# HARE_schematic_10172017.net
KiCad netlist of a schematic drawn in EAGLE
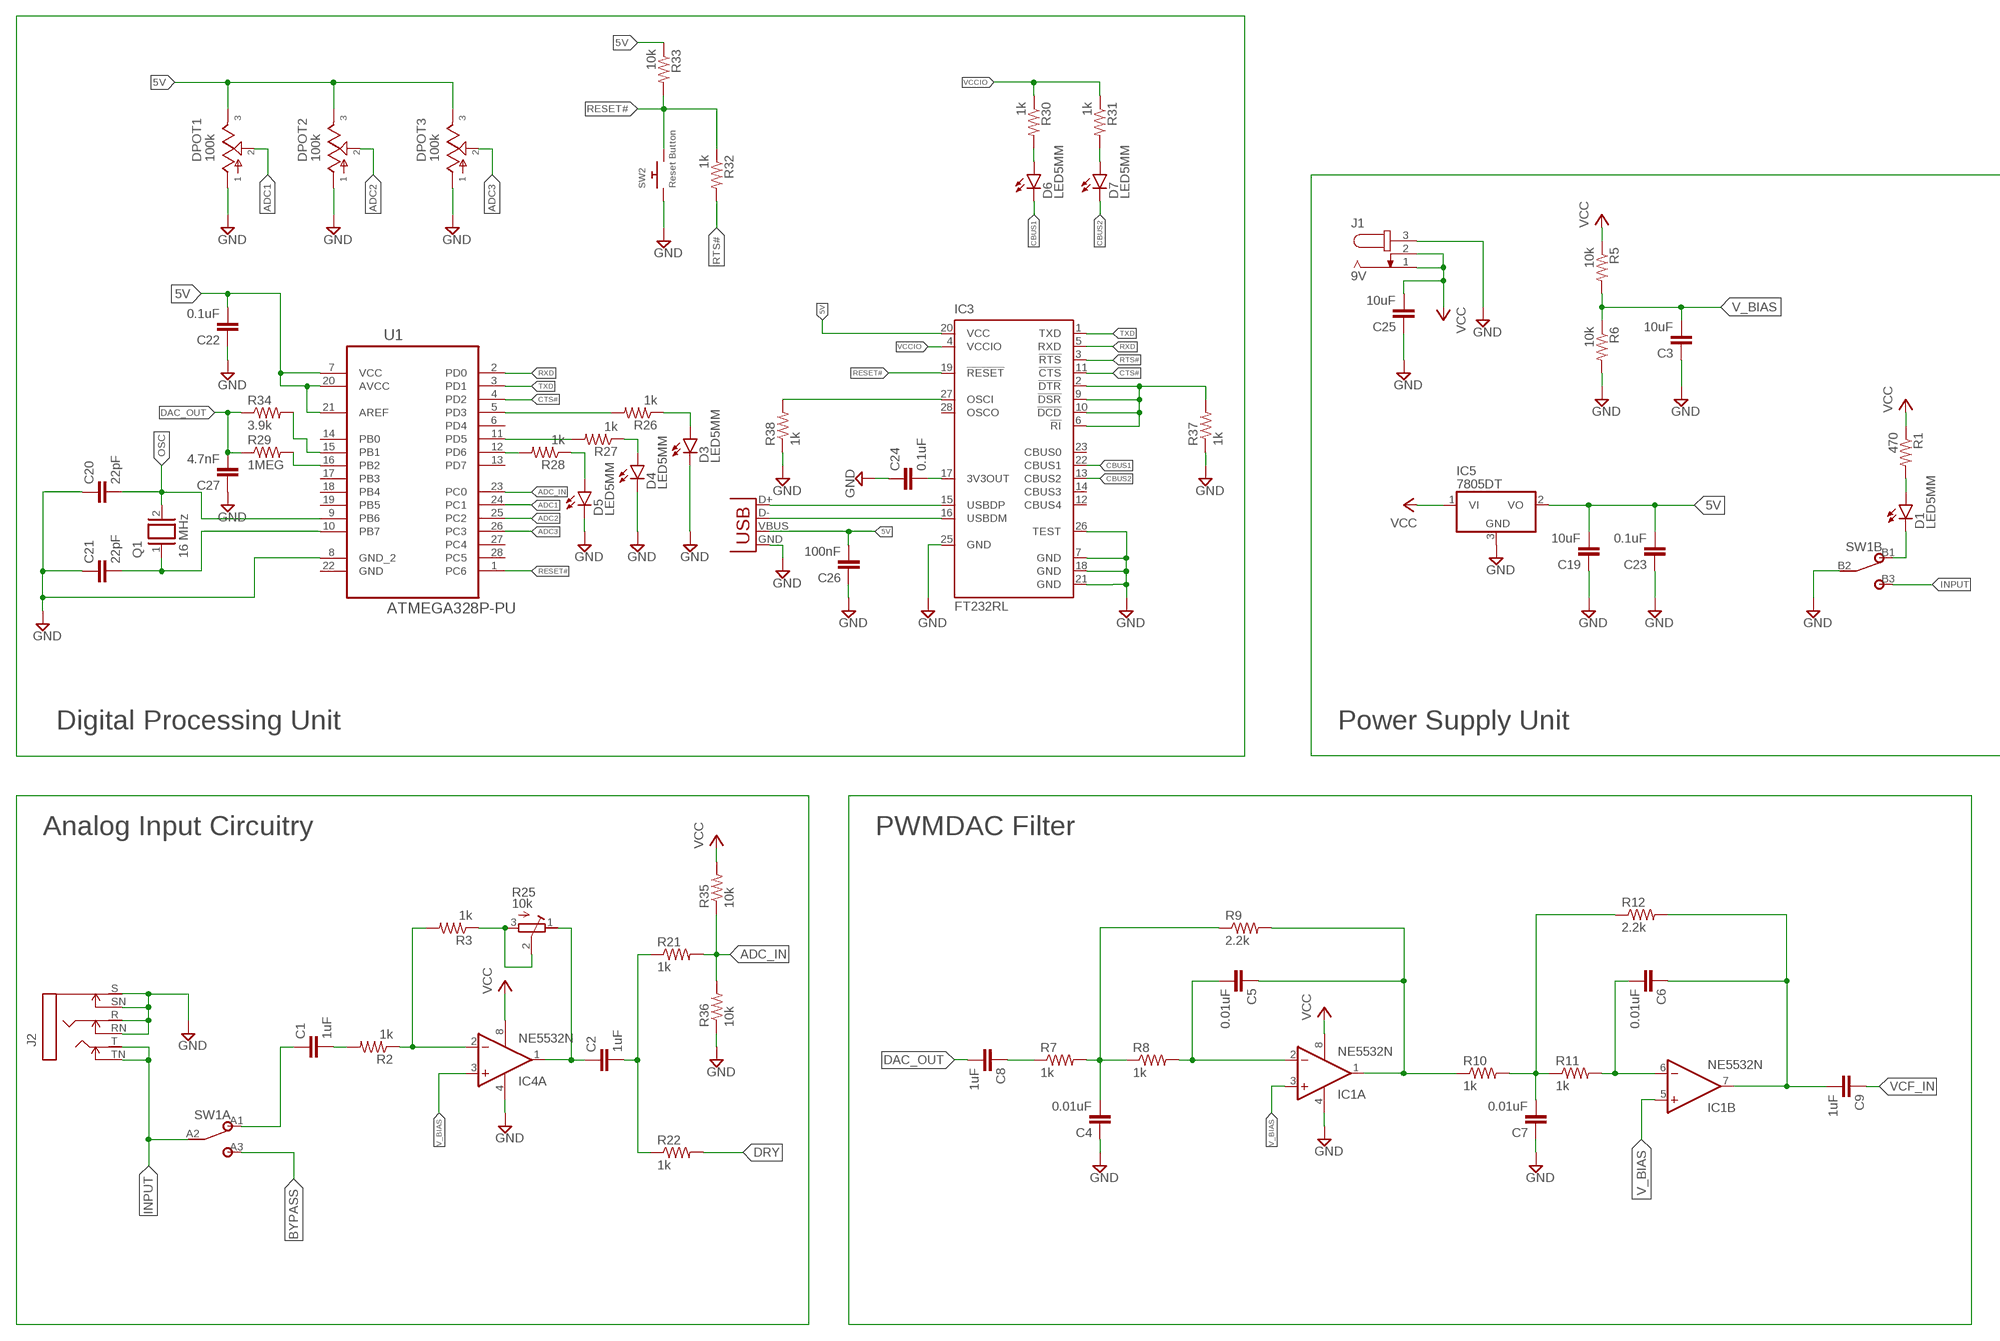
[diagram p0: schematic, sheet 1, part 1 of 2]
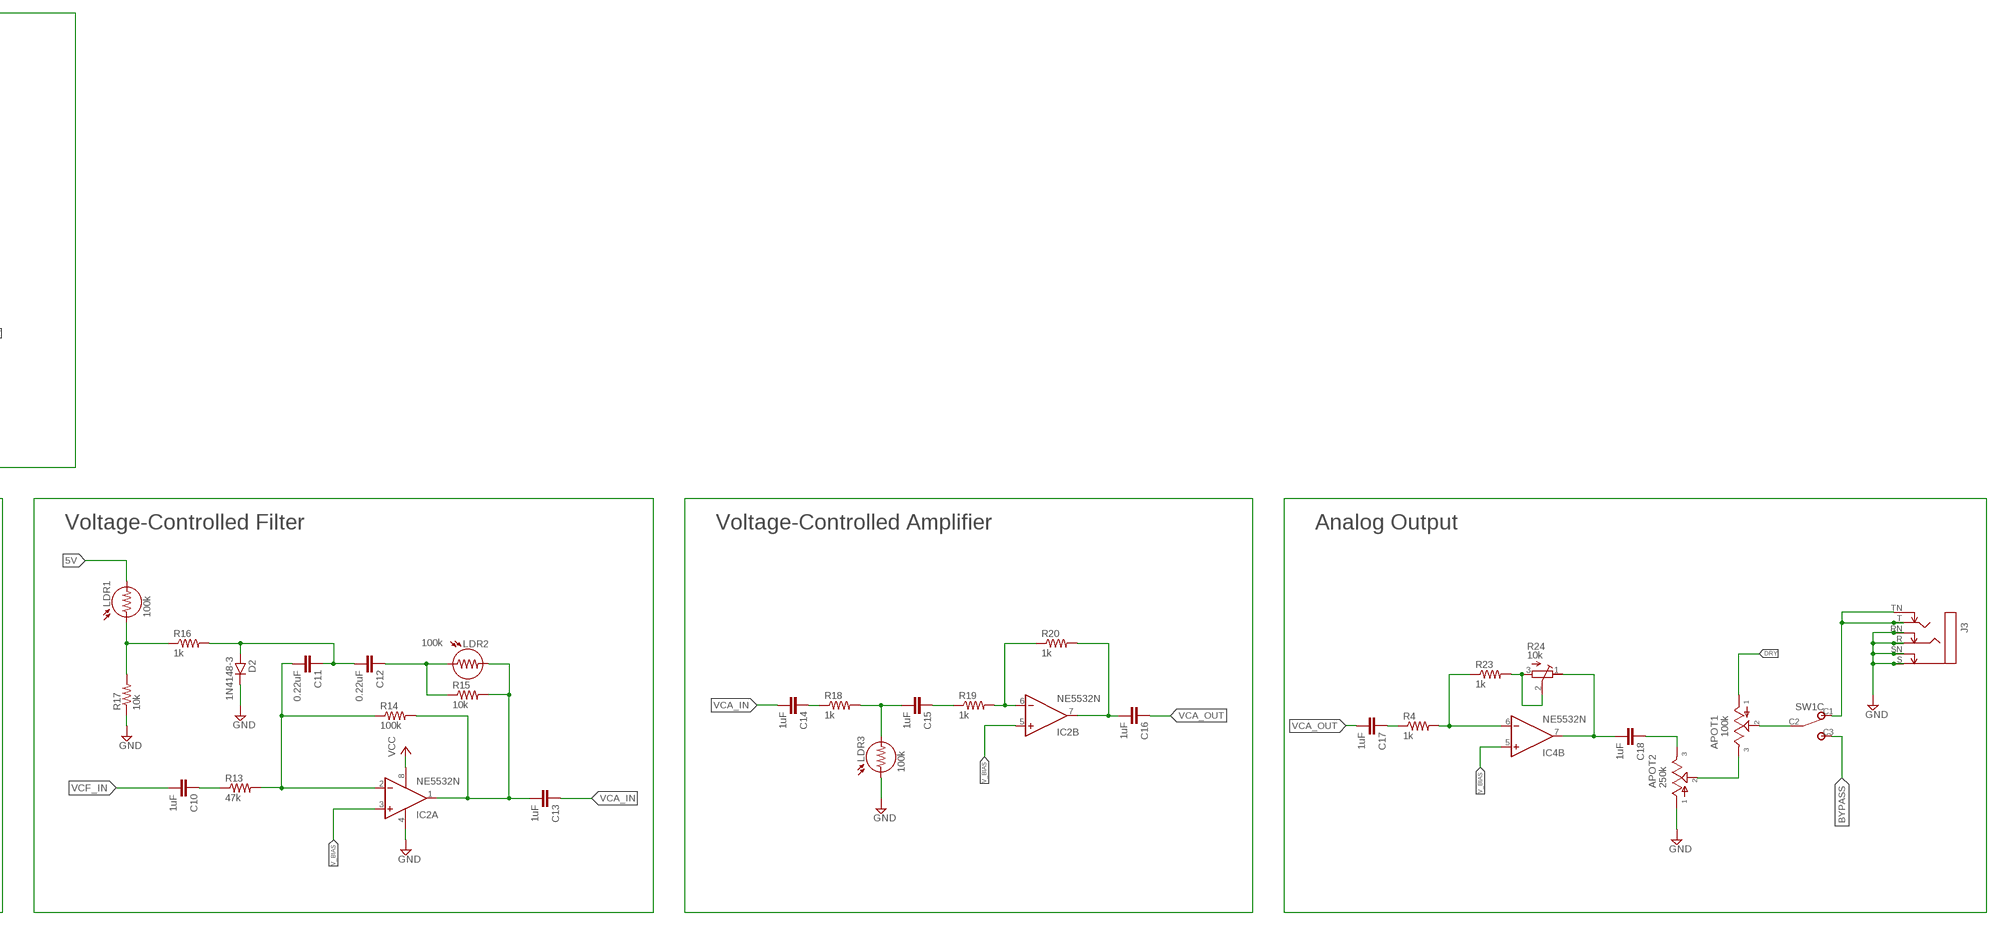
[diagram p1: schematic, sheet 1, part 2 of 2]

(export (version "E")
  (design (tool "Eeschema 10.0.6"))
  (components
    (comp (ref "APOT1")
      (value "100k")
      (footprint "eagle-import:16MM-SQUARE")
      (libsource (lib "eagle-import") (part "POTS"))
    )
    (comp (ref "APOT2")
      (value "250k")
      (footprint "eagle-import:16MM-SQUARE")
      (libsource (lib "eagle-import") (part "POTS"))
    )
    (comp (ref "C1")
      (value "1uF")
      (footprint "eagle-import:C0805K")
      (libsource (lib "eagle-import") (part "C-EUC0805K"))
    )
    (comp (ref "C2")
      (value "1uF")
      (footprint "eagle-import:C0805K")
      (libsource (lib "eagle-import") (part "C-EUC0805K"))
    )
    (comp (ref "C3")
      (value "10uF")
      (footprint "eagle-import:C0805K")
      (libsource (lib "eagle-import") (part "C-EUC0805K"))
    )
    (comp (ref "C4")
      (value "0.01uF")
      (footprint "eagle-import:C0805K")
      (libsource (lib "eagle-import") (part "C-EUC0805K"))
    )
    (comp (ref "C5")
      (value "0.01uF")
      (footprint "eagle-import:C0805K")
      (libsource (lib "eagle-import") (part "C-EUC0805K"))
    )
    (comp (ref "C6")
      (value "0.01uF")
      (footprint "eagle-import:C0805K")
      (libsource (lib "eagle-import") (part "C-EUC0805K"))
    )
    (comp (ref "C7")
      (value "0.01uF")
      (footprint "eagle-import:C0805K")
      (libsource (lib "eagle-import") (part "C-EUC0805K"))
    )
    (comp (ref "C8")
      (value "1uF")
      (footprint "eagle-import:C0805K")
      (libsource (lib "eagle-import") (part "C-EUC0805K"))
    )
    (comp (ref "C9")
      (value "1uF")
      (footprint "eagle-import:C0805K")
      (libsource (lib "eagle-import") (part "C-EUC0805K"))
    )
    (comp (ref "C10")
      (value "1uF")
      (footprint "eagle-import:C0805K")
      (libsource (lib "eagle-import") (part "C-EUC0805K"))
    )
    (comp (ref "C11")
      (value "0.22uF")
      (footprint "eagle-import:C0805K")
      (libsource (lib "eagle-import") (part "C-EUC0805K"))
    )
    (comp (ref "C12")
      (value "0.22uF")
      (footprint "eagle-import:C0805K")
      (libsource (lib "eagle-import") (part "C-EUC0805K"))
    )
    (comp (ref "C13")
      (value "1uF")
      (footprint "eagle-import:C0805K")
      (libsource (lib "eagle-import") (part "C-EUC0805K"))
    )
    (comp (ref "C14")
      (value "1uF")
      (footprint "eagle-import:C0805K")
      (libsource (lib "eagle-import") (part "C-EUC0805K"))
    )
    (comp (ref "C15")
      (value "1uF")
      (footprint "eagle-import:C0805K")
      (libsource (lib "eagle-import") (part "C-EUC0805K"))
    )
    (comp (ref "C16")
      (value "1uF")
      (footprint "eagle-import:C0805K")
      (libsource (lib "eagle-import") (part "C-EUC0805K"))
    )
    (comp (ref "C17")
      (value "1uF")
      (footprint "eagle-import:C0805K")
      (libsource (lib "eagle-import") (part "C-EUC0805K"))
    )
    (comp (ref "C18")
      (value "1uF")
      (footprint "eagle-import:C0805K")
      (libsource (lib "eagle-import") (part "C-EUC0805K"))
    )
    (comp (ref "C19")
      (value "10uF")
      (footprint "eagle-import:C0805K")
      (libsource (lib "eagle-import") (part "C-EUC0805K"))
    )
    (comp (ref "C20")
      (value "22pF")
      (footprint "eagle-import:C0805K")
      (libsource (lib "eagle-import") (part "C-EUC0805K"))
    )
    (comp (ref "C21")
      (value "22pF")
      (footprint "eagle-import:C0805K")
      (libsource (lib "eagle-import") (part "C-EUC0805K"))
    )
    (comp (ref "C22")
      (value "0.1uF")
      (footprint "eagle-import:C0805K")
      (libsource (lib "eagle-import") (part "C-EUC0805K"))
    )
    (comp (ref "C23")
      (value "0.1uF")
      (footprint "eagle-import:C0805K")
      (libsource (lib "eagle-import") (part "C-EUC0805K"))
    )
    (comp (ref "C24")
      (value "0.1uF")
      (footprint "eagle-import:C0805K")
      (libsource (lib "eagle-import") (part "C-EUC0805K"))
    )
    (comp (ref "C25")
      (value "10uF")
      (footprint "eagle-import:C0805K")
      (libsource (lib "eagle-import") (part "C-EUC0805K"))
    )
    (comp (ref "C26")
      (value "100nF")
      (footprint "eagle-import:C0805K")
      (libsource (lib "eagle-import") (part "C-EUC0805K"))
    )
    (comp (ref "C27")
      (value "4.7nF")
      (footprint "eagle-import:C0805K")
      (libsource (lib "eagle-import") (part "C-EUC0805K"))
    )
    (comp (ref "D1")
      (value "LED5MM")
      (footprint "eagle-import:LED5MM")
      (libsource (lib "eagle-import") (part "LED5MM"))
    )
    (comp (ref "D2")
      (value "1N4148-3")
      (footprint "eagle-import:DO35-3")
      (libsource (lib "eagle-import") (part "1N4148-3"))
    )
    (comp (ref "D3")
      (value "LED5MM")
      (footprint "eagle-import:LED5MM")
      (libsource (lib "eagle-import") (part "LED5MM"))
    )
    (comp (ref "D4")
      (value "LED5MM")
      (footprint "eagle-import:LED5MM")
      (libsource (lib "eagle-import") (part "LED5MM"))
    )
    (comp (ref "D5")
      (value "LED5MM")
      (footprint "eagle-import:LED5MM")
      (libsource (lib "eagle-import") (part "LED5MM"))
    )
    (comp (ref "D6")
      (value "LED5MM")
      (footprint "eagle-import:LED5MM")
      (libsource (lib "eagle-import") (part "LED5MM"))
    )
    (comp (ref "D7")
      (value "LED5MM")
      (footprint "eagle-import:LED5MM")
      (libsource (lib "eagle-import") (part "LED5MM"))
    )
    (comp (ref "DPOT1")
      (value "100k")
      (footprint "eagle-import:16MM-SQUARE")
      (libsource (lib "eagle-import") (part "POTS"))
    )
    (comp (ref "DPOT2")
      (value "100k")
      (footprint "eagle-import:16MM-SQUARE")
      (libsource (lib "eagle-import") (part "POTS"))
    )
    (comp (ref "DPOT3")
      (value "100k")
      (footprint "eagle-import:16MM-SQUARE")
      (libsource (lib "eagle-import") (part "POTS"))
    )
    (comp (ref "IC1")
      (value "NE5532N")
      (footprint "eagle-import:DIL08")
      (libsource (lib "eagle-import") (part "NE5532N"))
    )
    (comp (ref "IC2")
      (value "NE5532N")
      (footprint "eagle-import:DIL08")
      (libsource (lib "eagle-import") (part "NE5532N"))
    )
    (comp (ref "IC3")
      (value "FT232RL")
      (footprint "eagle-import:SSOP28")
      (libsource (lib "eagle-import") (part "FT232RL"))
    )
    (comp (ref "IC4")
      (value "NE5532N")
      (footprint "eagle-import:DIL08")
      (libsource (lib "eagle-import") (part "NE5532N"))
    )
    (comp (ref "IC5")
      (value "7805DT")
      (footprint "eagle-import:TO252")
      (libsource (lib "eagle-import") (part "78DT05"))
    )
    (comp (ref "J1")
      (value "9V")
      (footprint "eagle-import:SPC4078")
      (libsource (lib "eagle-import") (part "JACK-PLUG1"))
    )
    (comp (ref "J2")
      (value "STEREOSW")
      (footprint "eagle-import:NMJ6HCD2")
      (libsource (lib "eagle-import") (part "STEREOSW"))
    )
    (comp (ref "J3")
      (value "STEREOSW")
      (footprint "eagle-import:NMJ6HCD2")
      (libsource (lib "eagle-import") (part "STEREOSW"))
    )
    (comp (ref "LDR1")
      (value "100k")
      (footprint "eagle-import:LDR338-54C")
      (libsource (lib "eagle-import") (part "LDR5MM"))
    )
    (comp (ref "LDR2")
      (value "100k")
      (footprint "eagle-import:LDR338-54C")
      (libsource (lib "eagle-import") (part "LDR5MM"))
    )
    (comp (ref "LDR3")
      (value "100k")
      (footprint "eagle-import:LDR338-54C")
      (libsource (lib "eagle-import") (part "LDR5MM"))
    )
    (comp (ref "Q1")
      (value "16 MHz")
      (footprint "eagle-import:QS")
      (libsource (lib "eagle-import") (part "XTAL/S"))
    )
    (comp (ref "R1")
      (value "470")
      (footprint "eagle-import:M0805")
      (libsource (lib "eagle-import") (part "R-US_M0805"))
    )
    (comp (ref "R2")
      (value "1k")
      (footprint "eagle-import:R0805")
      (libsource (lib "eagle-import") (part "resistor_R-US_R0805"))
    )
    (comp (ref "R3")
      (value "1k")
      (footprint "eagle-import:R0805")
      (libsource (lib "eagle-import") (part "resistor_R-US_R0805"))
    )
    (comp (ref "R4")
      (value "1k")
      (footprint "eagle-import:R0805")
      (libsource (lib "eagle-import") (part "resistor_R-US_R0805"))
    )
    (comp (ref "R5")
      (value "10k")
      (footprint "eagle-import:M0805")
      (libsource (lib "eagle-import") (part "R-US_M0805"))
    )
    (comp (ref "R6")
      (value "10k")
      (footprint "eagle-import:M0805")
      (libsource (lib "eagle-import") (part "R-US_M0805"))
    )
    (comp (ref "R7")
      (value "1k")
      (footprint "eagle-import:R0805")
      (libsource (lib "eagle-import") (part "resistor_R-US_R0805"))
    )
    (comp (ref "R8")
      (value "1k")
      (footprint "eagle-import:R0805")
      (libsource (lib "eagle-import") (part "resistor_R-US_R0805"))
    )
    (comp (ref "R9")
      (value "2.2k")
      (footprint "eagle-import:R0805")
      (libsource (lib "eagle-import") (part "resistor_R-US_R0805"))
    )
    (comp (ref "R10")
      (value "1k")
      (footprint "eagle-import:R0805")
      (libsource (lib "eagle-import") (part "resistor_R-US_R0805"))
    )
    (comp (ref "R11")
      (value "1k")
      (footprint "eagle-import:R0805")
      (libsource (lib "eagle-import") (part "resistor_R-US_R0805"))
    )
    (comp (ref "R12")
      (value "2.2k")
      (footprint "eagle-import:R0805")
      (libsource (lib "eagle-import") (part "resistor_R-US_R0805"))
    )
    (comp (ref "R13")
      (value "47k")
      (footprint "eagle-import:R0805")
      (libsource (lib "eagle-import") (part "resistor_R-US_R0805"))
    )
    (comp (ref "R14")
      (value "100k")
      (footprint "eagle-import:R0805")
      (libsource (lib "eagle-import") (part "resistor_R-US_R0805"))
    )
    (comp (ref "R15")
      (value "10k")
      (footprint "eagle-import:R0805")
      (libsource (lib "eagle-import") (part "resistor_R-US_R0805"))
    )
    (comp (ref "R16")
      (value "1k")
      (footprint "eagle-import:R0805")
      (libsource (lib "eagle-import") (part "resistor_R-US_R0805"))
    )
    (comp (ref "R17")
      (value "10k")
      (footprint "eagle-import:R0805")
      (libsource (lib "eagle-import") (part "resistor_R-US_R0805"))
    )
    (comp (ref "R18")
      (value "1k")
      (footprint "eagle-import:R0805")
      (libsource (lib "eagle-import") (part "resistor_R-US_R0805"))
    )
    (comp (ref "R19")
      (value "1k")
      (footprint "eagle-import:R0805")
      (libsource (lib "eagle-import") (part "resistor_R-US_R0805"))
    )
    (comp (ref "R20")
      (value "1k")
      (footprint "eagle-import:R0805")
      (libsource (lib "eagle-import") (part "resistor_R-US_R0805"))
    )
    (comp (ref "R21")
      (value "1k")
      (footprint "eagle-import:R0805")
      (libsource (lib "eagle-import") (part "resistor_R-US_R0805"))
    )
    (comp (ref "R22")
      (value "1k")
      (footprint "eagle-import:R0805")
      (libsource (lib "eagle-import") (part "resistor_R-US_R0805"))
    )
    (comp (ref "R23")
      (value "1k")
      (footprint "eagle-import:R0805")
      (libsource (lib "eagle-import") (part "resistor_R-US_R0805"))
    )
    (comp (ref "R24")
      (value "10k")
      (footprint "eagle-import:RTRIM3314G")
      (libsource (lib "eagle-import") (part "R-TRIMM3314G"))
    )
    (comp (ref "R25")
      (value "10k")
      (footprint "eagle-import:RTRIM3314G")
      (libsource (lib "eagle-import") (part "R-TRIMM3314G"))
    )
    (comp (ref "R26")
      (value "1k")
      (footprint "eagle-import:R0805")
      (libsource (lib "eagle-import") (part "resistor_R-US_R0805"))
    )
    (comp (ref "R27")
      (value "1k")
      (footprint "eagle-import:R0805")
      (libsource (lib "eagle-import") (part "resistor_R-US_R0805"))
    )
    (comp (ref "R28")
      (value "1k")
      (footprint "eagle-import:R0805")
      (libsource (lib "eagle-import") (part "resistor_R-US_R0805"))
    )
    (comp (ref "R29")
      (value "1MEG")
      (footprint "eagle-import:R0805")
      (libsource (lib "eagle-import") (part "resistor_R-US_R0805"))
    )
    (comp (ref "R30")
      (value "1k")
      (footprint "eagle-import:R0805")
      (libsource (lib "eagle-import") (part "resistor_R-US_R0805"))
    )
    (comp (ref "R31")
      (value "1k")
      (footprint "eagle-import:R0805")
      (libsource (lib "eagle-import") (part "resistor_R-US_R0805"))
    )
    (comp (ref "R32")
      (value "1k")
      (footprint "eagle-import:R0805")
      (libsource (lib "eagle-import") (part "resistor_R-US_R0805"))
    )
    (comp (ref "R33")
      (value "10k")
      (footprint "eagle-import:R0805")
      (libsource (lib "eagle-import") (part "resistor_R-US_R0805"))
    )
    (comp (ref "R34")
      (value "3.9k")
      (footprint "eagle-import:R0805")
      (libsource (lib "eagle-import") (part "resistor_R-US_R0805"))
    )
    (comp (ref "R35")
      (value "10k")
      (footprint "eagle-import:R0805")
      (libsource (lib "eagle-import") (part "resistor_R-US_R0805"))
    )
    (comp (ref "R36")
      (value "10k")
      (footprint "eagle-import:R0805")
      (libsource (lib "eagle-import") (part "resistor_R-US_R0805"))
    )
    (comp (ref "R37")
      (value "1k")
      (footprint "eagle-import:R0805")
      (libsource (lib "eagle-import") (part "resistor_R-US_R0805"))
    )
    (comp (ref "R38")
      (value "1k")
      (footprint "eagle-import:R0805")
      (libsource (lib "eagle-import") (part "resistor_R-US_R0805"))
    )
    (comp (ref "SW1")
      (value "3PDTBLUE")
      (footprint "eagle-import:CHINABLUE")
      (libsource (lib "eagle-import") (part "3PDTBLUE"))
    )
    (comp (ref "SW2")
      (value "Reset Button")
      (footprint "eagle-import:PUSHBUTTON_SMD_SJ")
      (libsource (lib "eagle-import") (part "SWITCH_PUSHBUTTONSOFTTOUCHSMD_SJ"))
    )
    (comp (ref "U1")
      (value "ATMEGA328P-PU")
      (footprint "eagle-import:DIP254P762X457-28")
      (libsource (lib "eagle-import") (part "ATMEGA328P-PU"))
    )
    (comp (ref "X2")
      (value "USB-B-H")
      (footprint "eagle-import:USB-B-H")
      (libsource (lib "eagle-import") (part "USB-B-H"))
    )
  )
  (nets
    (net (code "1") (name "5V") (class "Default")
      (node (ref "C19") (pin "2") (pinfunction "2_2") (pintype "passive"))
      (node (ref "C22") (pin "2") (pinfunction "2_2") (pintype "passive"))
      (node (ref "C23") (pin "2") (pinfunction "2_2") (pintype "passive"))
      (node (ref "C26") (pin "2") (pinfunction "2_2") (pintype "passive"))
      (node (ref "DPOT1") (pin "3") (pinfunction "3_3") (pintype "passive"))
      (node (ref "DPOT2") (pin "3") (pinfunction "3_3") (pintype "passive"))
      (node (ref "DPOT3") (pin "3") (pinfunction "3_3") (pintype "passive"))
      (node (ref "IC3") (pin "20") (pinfunction "VCC_20") (pintype "power_in"))
      (node (ref "IC5") (pin "2") (pinfunction "VO_2") (pintype "passive"))
      (node (ref "LDR1") (pin "2") (pinfunction "2_2") (pintype "passive"))
      (node (ref "R33") (pin "1") (pinfunction "1_1") (pintype "passive"))
      (node (ref "U1") (pin "20") (pinfunction "AVCC_20") (pintype "power_in"))
      (node (ref "U1") (pin "21") (pinfunction "AREF_21") (pintype "input"))
      (node (ref "U1") (pin "7") (pinfunction "VCC_7") (pintype "power_in"))
      (node (ref "X2") (pin "VBUS") (pinfunction "VBUS_VBUS") (pintype "bidirectional"))
    )
    (net (code "2") (name "ADC1") (class "Default")
      (node (ref "DPOT1") (pin "2") (pinfunction "2_2") (pintype "passive"))
      (node (ref "U1") (pin "24") (pinfunction "PC1_24") (pintype "bidirectional"))
    )
    (net (code "3") (name "ADC2") (class "Default")
      (node (ref "DPOT2") (pin "2") (pinfunction "2_2") (pintype "passive"))
      (node (ref "U1") (pin "25") (pinfunction "PC2_25") (pintype "bidirectional"))
    )
    (net (code "4") (name "ADC3") (class "Default")
      (node (ref "DPOT3") (pin "2") (pinfunction "2_2") (pintype "passive"))
      (node (ref "U1") (pin "26") (pinfunction "PC3_26") (pintype "bidirectional"))
    )
    (net (code "5") (name "ADC_IN") (class "Default")
      (node (ref "R21") (pin "2") (pinfunction "2_2") (pintype "passive"))
      (node (ref "R35") (pin "1") (pinfunction "1_1") (pintype "passive"))
      (node (ref "R36") (pin "2") (pinfunction "2_2") (pintype "passive"))
      (node (ref "U1") (pin "23") (pinfunction "PC0_23") (pintype "bidirectional"))
    )
    (net (code "6") (name "BYPASS") (class "Default")
      (node (ref "SW1") (pin "A3") (pinfunction "3_A3") (pintype "passive"))
      (node (ref "SW1") (pin "C3") (pinfunction "3_C3") (pintype "passive"))
    )
    (net (code "7") (name "CBUS1") (class "Default")
      (node (ref "D6") (pin "K") (pinfunction "C_K") (pintype "passive"))
      (node (ref "IC3") (pin "22") (pinfunction "CBUS1_22") (pintype "bidirectional"))
    )
    (net (code "8") (name "CBUS2") (class "Default")
      (node (ref "D7") (pin "K") (pinfunction "C_K") (pintype "passive"))
      (node (ref "IC3") (pin "13") (pinfunction "CBUS2_13") (pintype "bidirectional"))
    )
    (net (code "9") (name "CTS#") (class "Default")
      (node (ref "IC3") (pin "11") (pinfunction "~{CTS}_11") (pintype "input"))
      (node (ref "U1") (pin "4") (pinfunction "PD2_4") (pintype "bidirectional"))
    )
    (net (code "10") (name "DAC_OUT") (class "Default")
      (node (ref "C27") (pin "2") (pinfunction "2_2") (pintype "passive"))
      (node (ref "C8") (pin "2") (pinfunction "2_2") (pintype "passive"))
      (node (ref "R29") (pin "1") (pinfunction "1_1") (pintype "passive"))
      (node (ref "R34") (pin "1") (pinfunction "1_1") (pintype "passive"))
    )
    (net (code "11") (name "DRY") (class "Default")
      (node (ref "APOT1") (pin "1") (pinfunction "1_1") (pintype "passive"))
      (node (ref "R22") (pin "2") (pinfunction "2_2") (pintype "passive"))
    )
    (net (code "12") (name "GND") (class "Default")
      (node (ref "APOT2") (pin "1") (pinfunction "1_1") (pintype "passive"))
      (node (ref "C19") (pin "1") (pinfunction "1_1") (pintype "passive"))
      (node (ref "C20") (pin "1") (pinfunction "1_1") (pintype "passive"))
      (node (ref "C21") (pin "1") (pinfunction "1_1") (pintype "passive"))
      (node (ref "C22") (pin "1") (pinfunction "1_1") (pintype "passive"))
      (node (ref "C23") (pin "1") (pinfunction "1_1") (pintype "passive"))
      (node (ref "C24") (pin "1") (pinfunction "1_1") (pintype "passive"))
      (node (ref "C25") (pin "1") (pinfunction "1_1") (pintype "passive"))
      (node (ref "C26") (pin "1") (pinfunction "1_1") (pintype "passive"))
      (node (ref "C27") (pin "1") (pinfunction "1_1") (pintype "passive"))
      (node (ref "C3") (pin "1") (pinfunction "1_1") (pintype "passive"))
      (node (ref "C4") (pin "1") (pinfunction "1_1") (pintype "passive"))
      (node (ref "C7") (pin "1") (pinfunction "1_1") (pintype "passive"))
      (node (ref "D2") (pin "C") (pinfunction "C_C") (pintype "passive"))
      (node (ref "D3") (pin "K") (pinfunction "C_K") (pintype "passive"))
      (node (ref "D4") (pin "K") (pinfunction "C_K") (pintype "passive"))
      (node (ref "D5") (pin "K") (pinfunction "C_K") (pintype "passive"))
      (node (ref "DPOT1") (pin "1") (pinfunction "1_1") (pintype "passive"))
      (node (ref "DPOT2") (pin "1") (pinfunction "1_1") (pintype "passive"))
      (node (ref "DPOT3") (pin "1") (pinfunction "1_1") (pintype "passive"))
      (node (ref "IC1") (pin "4") (pinfunction "V-_4") (pintype "power_in"))
      (node (ref "IC2") (pin "4") (pinfunction "V-_4") (pintype "power_in"))
      (node (ref "IC3") (pin "18") (pinfunction "GND_18") (pintype "power_in"))
      (node (ref "IC3") (pin "21") (pinfunction "GND_21") (pintype "power_in"))
      (node (ref "IC3") (pin "25") (pinfunction "GND_25") (pintype "power_in"))
      (node (ref "IC3") (pin "26") (pinfunction "TEST_26") (pintype "input"))
      (node (ref "IC3") (pin "7") (pinfunction "GND_7") (pintype "power_in"))
      (node (ref "IC4") (pin "4") (pinfunction "V-_4") (pintype "power_in"))
      (node (ref "IC5") (pin "3") (pinfunction "GND_3") (pintype "passive"))
      (node (ref "J1") (pin "3") (pinfunction "3_3") (pintype "passive"))
      (node (ref "J2") (pin "R") (pinfunction "R_R") (pintype "passive"))
      (node (ref "J2") (pin "RN") (pinfunction "RN_RN") (pintype "passive"))
      (node (ref "J2") (pin "S") (pinfunction "S_S") (pintype "passive"))
      (node (ref "J2") (pin "SN") (pinfunction "SN_SN") (pintype "passive"))
      (node (ref "J3") (pin "R") (pinfunction "R_R") (pintype "passive"))
      (node (ref "J3") (pin "RN") (pinfunction "RN_RN") (pintype "passive"))
      (node (ref "J3") (pin "S") (pinfunction "S_S") (pintype "passive"))
      (node (ref "J3") (pin "SN") (pinfunction "SN_SN") (pintype "passive"))
      (node (ref "LDR3") (pin "1") (pinfunction "1_1") (pintype "passive"))
      (node (ref "R17") (pin "1") (pinfunction "1_1") (pintype "passive"))
      (node (ref "R36") (pin "1") (pinfunction "1_1") (pintype "passive"))
      (node (ref "R37") (pin "1") (pinfunction "1_1") (pintype "passive"))
      (node (ref "R38") (pin "1") (pinfunction "1_1") (pintype "passive"))
      (node (ref "R6") (pin "2") (pinfunction "2_2") (pintype "passive"))
      (node (ref "SW1") (pin "B2") (pinfunction "2_B2") (pintype "passive"))
      (node (ref "SW2") (pin "P$1") (pinfunction "P$1_P$1") (pintype "passive"))
      (node (ref "U1") (pin "8") (pinfunction "GND_2_8") (pintype "passive"))
      (node (ref "X2") (pin "GND") (pinfunction "GND_GND") (pintype "bidirectional"))
    )
    (net (code "13") (name "INPUT") (class "Default")
      (node (ref "J2") (pin "T") (pinfunction "T_T") (pintype "passive"))
      (node (ref "J2") (pin "TN") (pinfunction "TN_TN") (pintype "passive"))
      (node (ref "SW1") (pin "A2") (pinfunction "2_A2") (pintype "passive"))
      (node (ref "SW1") (pin "B3") (pinfunction "3_B3") (pintype "passive"))
    )
    (net (code "14") (name "Net-(APOT1-Pad3)") (class "Default")
      (node (ref "APOT1") (pin "3") (pinfunction "3_3") (pintype "passive"))
      (node (ref "APOT2") (pin "2") (pinfunction "2_2") (pintype "passive"))
    )
    (net (code "15") (name "Net-(APOT2-Pad3)") (class "Default")
      (node (ref "APOT2") (pin "3") (pinfunction "3_3") (pintype "passive"))
      (node (ref "C18") (pin "1") (pinfunction "1_1") (pintype "passive"))
    )
    (net (code "16") (name "Net-(C1-Pad2)") (class "Default")
      (node (ref "C1") (pin "2") (pinfunction "2_2") (pintype "passive"))
      (node (ref "R2") (pin "2") (pinfunction "2_2") (pintype "passive"))
    )
    (net (code "17") (name "Net-(C2-Pad2)") (class "Default")
      (node (ref "C2") (pin "2") (pinfunction "2_2") (pintype "passive"))
      (node (ref "R21") (pin "1") (pinfunction "1_1") (pintype "passive"))
      (node (ref "R22") (pin "1") (pinfunction "1_1") (pintype "passive"))
    )
    (net (code "18") (name "Net-(C4-Pad2)") (class "Default")
      (node (ref "C4") (pin "2") (pinfunction "2_2") (pintype "passive"))
      (node (ref "R7") (pin "2") (pinfunction "2_2") (pintype "passive"))
      (node (ref "R8") (pin "1") (pinfunction "1_1") (pintype "passive"))
      (node (ref "R9") (pin "1") (pinfunction "1_1") (pintype "passive"))
    )
    (net (code "19") (name "Net-(C7-Pad2)") (class "Default")
      (node (ref "C7") (pin "2") (pinfunction "2_2") (pintype "passive"))
      (node (ref "R10") (pin "2") (pinfunction "2_2") (pintype "passive"))
      (node (ref "R11") (pin "1") (pinfunction "1_1") (pintype "passive"))
      (node (ref "R12") (pin "1") (pinfunction "1_1") (pintype "passive"))
    )
    (net (code "20") (name "Net-(C8-Pad1)") (class "Default")
      (node (ref "C8") (pin "1") (pinfunction "1_1") (pintype "passive"))
      (node (ref "R7") (pin "1") (pinfunction "1_1") (pintype "passive"))
    )
    (net (code "21") (name "Net-(C10-Pad1)") (class "Default")
      (node (ref "C10") (pin "1") (pinfunction "1_1") (pintype "passive"))
      (node (ref "R13") (pin "1") (pinfunction "1_1") (pintype "passive"))
    )
    (net (code "22") (name "Net-(C11-Pad1)") (class "Default")
      (node (ref "C11") (pin "1") (pinfunction "1_1") (pintype "passive"))
      (node (ref "C12") (pin "2") (pinfunction "2_2") (pintype "passive"))
      (node (ref "D2") (pin "A") (pinfunction "A_A") (pintype "passive"))
      (node (ref "R16") (pin "2") (pinfunction "2_2") (pintype "passive"))
    )
    (net (code "23") (name "Net-(C12-Pad1)") (class "Default")
      (node (ref "C12") (pin "1") (pinfunction "1_1") (pintype "passive"))
      (node (ref "LDR2") (pin "1") (pinfunction "1_1") (pintype "passive"))
      (node (ref "R15") (pin "1") (pinfunction "1_1") (pintype "passive"))
    )
    (net (code "24") (name "Net-(C14-Pad1)") (class "Default")
      (node (ref "C14") (pin "1") (pinfunction "1_1") (pintype "passive"))
      (node (ref "R18") (pin "1") (pinfunction "1_1") (pintype "passive"))
    )
    (net (code "25") (name "Net-(C15-Pad1)") (class "Default")
      (node (ref "C15") (pin "1") (pinfunction "1_1") (pintype "passive"))
      (node (ref "R19") (pin "1") (pinfunction "1_1") (pintype "passive"))
    )
    (net (code "26") (name "Net-(C15-Pad2)") (class "Default")
      (node (ref "C15") (pin "2") (pinfunction "2_2") (pintype "passive"))
      (node (ref "LDR3") (pin "2") (pinfunction "2_2") (pintype "passive"))
      (node (ref "R18") (pin "2") (pinfunction "2_2") (pintype "passive"))
    )
    (net (code "27") (name "Net-(C17-Pad1)") (class "Default")
      (node (ref "C17") (pin "1") (pinfunction "1_1") (pintype "passive"))
      (node (ref "R4") (pin "1") (pinfunction "1_1") (pintype "passive"))
    )
    (net (code "28") (name "Net-(D1-C)") (class "Default")
      (node (ref "D1") (pin "K") (pinfunction "C_K") (pintype "passive"))
      (node (ref "SW1") (pin "B1") (pinfunction "1_B1") (pintype "passive"))
    )
    (net (code "29") (name "Net-(D1-PadA)") (class "Default")
      (node (ref "D1") (pin "A") (pinfunction "A_A") (pintype "passive"))
      (node (ref "R1") (pin "2") (pinfunction "2_2") (pintype "passive"))
    )
    (net (code "30") (name "Net-(D3-PadA)") (class "Default")
      (node (ref "D3") (pin "A") (pinfunction "A_A") (pintype "passive"))
      (node (ref "R26") (pin "1") (pinfunction "1_1") (pintype "passive"))
    )
    (net (code "31") (name "Net-(D4-PadA)") (class "Default")
      (node (ref "D4") (pin "A") (pinfunction "A_A") (pintype "passive"))
      (node (ref "R27") (pin "1") (pinfunction "1_1") (pintype "passive"))
    )
    (net (code "32") (name "Net-(D5-PadA)") (class "Default")
      (node (ref "D5") (pin "A") (pinfunction "A_A") (pintype "passive"))
      (node (ref "R28") (pin "1") (pinfunction "1_1") (pintype "passive"))
    )
    (net (code "33") (name "Net-(D6-PadA)") (class "Default")
      (node (ref "D6") (pin "A") (pinfunction "A_A") (pintype "passive"))
      (node (ref "R30") (pin "2") (pinfunction "2_2") (pintype "passive"))
    )
    (net (code "34") (name "Net-(D7-PadA)") (class "Default")
      (node (ref "D7") (pin "A") (pinfunction "A_A") (pintype "passive"))
      (node (ref "R31") (pin "2") (pinfunction "2_2") (pintype "passive"))
    )
    (net (code "35") (name "Net-(IC1A--IN)") (class "Default")
      (node (ref "C5") (pin "2") (pinfunction "2_2") (pintype "passive"))
      (node (ref "IC1") (pin "2") (pinfunction "-IN_2") (pintype "input"))
      (node (ref "R8") (pin "2") (pinfunction "2_2") (pintype "passive"))
    )
    (net (code "36") (name "Net-(IC1A-OUT)") (class "Default")
      (node (ref "C5") (pin "1") (pinfunction "1_1") (pintype "passive"))
      (node (ref "IC1") (pin "1") (pinfunction "OUT_1") (pintype "output"))
      (node (ref "R10") (pin "1") (pinfunction "1_1") (pintype "passive"))
      (node (ref "R9") (pin "2") (pinfunction "2_2") (pintype "passive"))
    )
    (net (code "37") (name "Net-(IC1B--IN)") (class "Default")
      (node (ref "C6") (pin "2") (pinfunction "2_2") (pintype "passive"))
      (node (ref "IC1") (pin "6") (pinfunction "-IN_6") (pintype "input"))
      (node (ref "R11") (pin "2") (pinfunction "2_2") (pintype "passive"))
    )
    (net (code "38") (name "Net-(IC1B-OUT)") (class "Default")
      (node (ref "C6") (pin "1") (pinfunction "1_1") (pintype "passive"))
      (node (ref "C9") (pin "2") (pinfunction "2_2") (pintype "passive"))
      (node (ref "IC1") (pin "7") (pinfunction "OUT_7") (pintype "output"))
      (node (ref "R12") (pin "2") (pinfunction "2_2") (pintype "passive"))
    )
    (net (code "39") (name "Net-(IC2A--IN)") (class "Default")
      (node (ref "C11") (pin "2") (pinfunction "2_2") (pintype "passive"))
      (node (ref "IC2") (pin "2") (pinfunction "-IN_2") (pintype "input"))
      (node (ref "R13") (pin "2") (pinfunction "2_2") (pintype "passive"))
      (node (ref "R14") (pin "1") (pinfunction "1_1") (pintype "passive"))
    )
    (net (code "40") (name "Net-(IC2A-OUT)") (class "Default")
      (node (ref "C13") (pin "2") (pinfunction "2_2") (pintype "passive"))
      (node (ref "IC2") (pin "1") (pinfunction "OUT_1") (pintype "output"))
      (node (ref "LDR2") (pin "2") (pinfunction "2_2") (pintype "passive"))
      (node (ref "R14") (pin "2") (pinfunction "2_2") (pintype "passive"))
      (node (ref "R15") (pin "2") (pinfunction "2_2") (pintype "passive"))
    )
    (net (code "41") (name "Net-(IC2B--IN)") (class "Default")
      (node (ref "IC2") (pin "6") (pinfunction "-IN_6") (pintype "input"))
      (node (ref "R19") (pin "2") (pinfunction "2_2") (pintype "passive"))
      (node (ref "R20") (pin "1") (pinfunction "1_1") (pintype "passive"))
    )
    (net (code "42") (name "Net-(IC2B-OUT)") (class "Default")
      (node (ref "C16") (pin "2") (pinfunction "2_2") (pintype "passive"))
      (node (ref "IC2") (pin "7") (pinfunction "OUT_7") (pintype "output"))
      (node (ref "R20") (pin "2") (pinfunction "2_2") (pintype "passive"))
    )
    (net (code "43") (name "Net-(IC3-3V3OUT)") (class "Default")
      (node (ref "C24") (pin "2") (pinfunction "2_2") (pintype "passive"))
      (node (ref "IC3") (pin "17") (pinfunction "3V3OUT_17") (pintype "output"))
    )
    (net (code "44") (name "Net-(IC3-OSCI)") (class "Default")
      (node (ref "IC3") (pin "27") (pinfunction "OSCI_27") (pintype "input"))
      (node (ref "R38") (pin "2") (pinfunction "2_2") (pintype "passive"))
    )
    (net (code "45") (name "Net-(IC3-USBDM)") (class "Default")
      (node (ref "IC3") (pin "16") (pinfunction "USBDM_16") (pintype "bidirectional"))
      (node (ref "X2") (pin "D-") (pinfunction "D-_D-") (pintype "bidirectional"))
    )
    (net (code "46") (name "Net-(IC3-USBDP)") (class "Default")
      (node (ref "IC3") (pin "15") (pinfunction "USBDP_15") (pintype "bidirectional"))
      (node (ref "X2") (pin "D+") (pinfunction "D+_D+") (pintype "bidirectional"))
    )
    (net (code "47") (name "Net-(IC3-~{DCD})") (class "Default")
      (node (ref "IC3") (pin "10") (pinfunction "~{DCD}_10") (pintype "input"))
      (node (ref "IC3") (pin "2") (pinfunction "~{DTR}_2") (pintype "output"))
      (node (ref "IC3") (pin "6") (pinfunction "~{RI}_6") (pintype "input"))
      (node (ref "IC3") (pin "9") (pinfunction "~{DSR}_9") (pintype "input"))
      (node (ref "R37") (pin "2") (pinfunction "2_2") (pintype "passive"))
    )
    (net (code "48") (name "Net-(IC4A--IN)") (class "Default")
      (node (ref "IC4") (pin "2") (pinfunction "-IN_2") (pintype "input"))
      (node (ref "R2") (pin "1") (pinfunction "1_1") (pintype "passive"))
      (node (ref "R3") (pin "2") (pinfunction "2_2") (pintype "passive"))
    )
    (net (code "49") (name "Net-(IC4A-OUT)") (class "Default")
      (node (ref "C2") (pin "1") (pinfunction "1_1") (pintype "passive"))
      (node (ref "IC4") (pin "1") (pinfunction "OUT_1") (pintype "output"))
      (node (ref "R25") (pin "1") (pinfunction "E_1") (pintype "passive"))
    )
    (net (code "50") (name "Net-(IC4B--IN)") (class "Default")
      (node (ref "IC4") (pin "6") (pinfunction "-IN_6") (pintype "input"))
      (node (ref "R23") (pin "1") (pinfunction "1_1") (pintype "passive"))
      (node (ref "R4") (pin "2") (pinfunction "2_2") (pintype "passive"))
    )
    (net (code "51") (name "Net-(IC4B-OUT)") (class "Default")
      (node (ref "C18") (pin "2") (pinfunction "2_2") (pintype "passive"))
      (node (ref "IC4") (pin "7") (pinfunction "OUT_7") (pintype "output"))
      (node (ref "R24") (pin "1") (pinfunction "E_1") (pintype "passive"))
    )
    (net (code "52") (name "Net-(LDR1-Pad1)") (class "Default")
      (node (ref "LDR1") (pin "1") (pinfunction "1_1") (pintype "passive"))
      (node (ref "R16") (pin "1") (pinfunction "1_1") (pintype "passive"))
      (node (ref "R17") (pin "2") (pinfunction "2_2") (pintype "passive"))
    )
    (net (code "53") (name "Net-(R24-A)") (class "Default")
      (node (ref "R23") (pin "2") (pinfunction "2_2") (pintype "passive"))
      (node (ref "R24") (pin "2") (pinfunction "S_2") (pintype "passive"))
      (node (ref "R24") (pin "3") (pinfunction "A_3") (pintype "passive"))
    )
    (net (code "54") (name "Net-(R25-A)") (class "Default")
      (node (ref "R25") (pin "2") (pinfunction "S_2") (pintype "passive"))
      (node (ref "R25") (pin "3") (pinfunction "A_3") (pintype "passive"))
      (node (ref "R3") (pin "1") (pinfunction "1_1") (pintype "passive"))
    )
    (net (code "55") (name "Net-(SW1A-1)") (class "Default")
      (node (ref "C1") (pin "1") (pinfunction "1_1") (pintype "passive"))
      (node (ref "SW1") (pin "A1") (pinfunction "1_A1") (pintype "passive"))
    )
    (net (code "56") (name "Net-(SW1C-1)") (class "Default")
      (node (ref "J3") (pin "T") (pinfunction "T_T") (pintype "passive"))
      (node (ref "J3") (pin "TN") (pinfunction "TN_TN") (pintype "passive"))
      (node (ref "SW1") (pin "C1") (pinfunction "1_C1") (pintype "passive"))
    )
    (net (code "57") (name "Net-(SW1C-2)") (class "Default")
      (node (ref "APOT1") (pin "2") (pinfunction "2_2") (pintype "passive"))
      (node (ref "SW1") (pin "C2") (pinfunction "2_C2") (pintype "passive"))
    )
    (net (code "58") (name "Net-(U1-PB1)") (class "Default")
      (node (ref "R34") (pin "2") (pinfunction "2_2") (pintype "passive"))
      (node (ref "U1") (pin "15") (pinfunction "PB1_15") (pintype "bidirectional"))
    )
    (net (code "59") (name "Net-(U1-PB2)") (class "Default")
      (node (ref "R29") (pin "2") (pinfunction "2_2") (pintype "passive"))
      (node (ref "U1") (pin "16") (pinfunction "PB2_16") (pintype "bidirectional"))
    )
    (net (code "60") (name "Net-(U1-PB7)") (class "Default")
      (node (ref "C21") (pin "2") (pinfunction "2_2") (pintype "passive"))
      (node (ref "Q1") (pin "1") (pinfunction "1_1") (pintype "passive"))
      (node (ref "U1") (pin "10") (pinfunction "PB7_10") (pintype "bidirectional"))
    )
    (net (code "61") (name "Net-(U1-PD3)") (class "Default")
      (node (ref "R26") (pin "2") (pinfunction "2_2") (pintype "passive"))
      (node (ref "U1") (pin "5") (pinfunction "PD3_5") (pintype "bidirectional"))
    )
    (net (code "62") (name "Net-(U1-PD5)") (class "Default")
      (node (ref "R27") (pin "2") (pinfunction "2_2") (pintype "passive"))
      (node (ref "U1") (pin "11") (pinfunction "PD5_11") (pintype "bidirectional"))
    )
    (net (code "63") (name "Net-(U1-PD6)") (class "Default")
      (node (ref "R28") (pin "2") (pinfunction "2_2") (pintype "passive"))
      (node (ref "U1") (pin "12") (pinfunction "PD6_12") (pintype "bidirectional"))
    )
    (net (code "64") (name "OSC") (class "Default")
      (node (ref "C20") (pin "2") (pinfunction "2_2") (pintype "passive"))
      (node (ref "Q1") (pin "2") (pinfunction "2_2") (pintype "passive"))
      (node (ref "U1") (pin "9") (pinfunction "PB6_9") (pintype "bidirectional"))
    )
    (net (code "65") (name "RESET#") (class "Default")
      (node (ref "IC3") (pin "19") (pinfunction "~{RESET}_19") (pintype "input"))
      (node (ref "R32") (pin "1") (pinfunction "1_1") (pintype "passive"))
      (node (ref "R33") (pin "2") (pinfunction "2_2") (pintype "passive"))
      (node (ref "SW2") (pin "P$2") (pinfunction "P$2_P$2") (pintype "passive"))
      (node (ref "U1") (pin "1") (pinfunction "PC6_1") (pintype "bidirectional"))
    )
    (net (code "66") (name "RTS#") (class "Default")
      (node (ref "IC3") (pin "3") (pinfunction "~{RTS}_3") (pintype "output"))
      (node (ref "R32") (pin "2") (pinfunction "2_2") (pintype "passive"))
    )
    (net (code "67") (name "RXD") (class "Default")
      (node (ref "IC3") (pin "5") (pinfunction "RXD_5") (pintype "input"))
      (node (ref "U1") (pin "2") (pinfunction "PD0_2") (pintype "bidirectional"))
    )
    (net (code "68") (name "TXD") (class "Default")
      (node (ref "IC3") (pin "1") (pinfunction "TXD_1") (pintype "output"))
      (node (ref "U1") (pin "3") (pinfunction "PD1_3") (pintype "bidirectional"))
    )
    (net (code "69") (name "VCA_IN") (class "Default")
      (node (ref "C13") (pin "1") (pinfunction "1_1") (pintype "passive"))
      (node (ref "C14") (pin "2") (pinfunction "2_2") (pintype "passive"))
    )
    (net (code "70") (name "VCA_OUT") (class "Default")
      (node (ref "C16") (pin "1") (pinfunction "1_1") (pintype "passive"))
      (node (ref "C17") (pin "2") (pinfunction "2_2") (pintype "passive"))
    )
    (net (code "71") (name "VCC") (class "Default")
      (node (ref "C25") (pin "2") (pinfunction "2_2") (pintype "passive"))
      (node (ref "IC1") (pin "8") (pinfunction "V+_8") (pintype "power_in"))
      (node (ref "IC2") (pin "8") (pinfunction "V+_8") (pintype "power_in"))
      (node (ref "IC4") (pin "8") (pinfunction "V+_8") (pintype "power_in"))
      (node (ref "IC5") (pin "1") (pinfunction "VI_1") (pintype "input"))
      (node (ref "J1") (pin "1") (pinfunction "1_1") (pintype "passive"))
      (node (ref "J1") (pin "2") (pinfunction "2_2") (pintype "passive"))
      (node (ref "R1") (pin "1") (pinfunction "1_1") (pintype "passive"))
      (node (ref "R35") (pin "2") (pinfunction "2_2") (pintype "passive"))
      (node (ref "R5") (pin "1") (pinfunction "1_1") (pintype "passive"))
    )
    (net (code "72") (name "VCCIO") (class "Default")
      (node (ref "IC3") (pin "4") (pinfunction "VCCIO_4") (pintype "power_in"))
      (node (ref "R30") (pin "1") (pinfunction "1_1") (pintype "passive"))
      (node (ref "R31") (pin "1") (pinfunction "1_1") (pintype "passive"))
    )
    (net (code "73") (name "VCF_IN") (class "Default")
      (node (ref "C10") (pin "2") (pinfunction "2_2") (pintype "passive"))
      (node (ref "C9") (pin "1") (pinfunction "1_1") (pintype "passive"))
    )
    (net (code "74") (name "V_BIAS") (class "Default")
      (node (ref "C3") (pin "2") (pinfunction "2_2") (pintype "passive"))
      (node (ref "IC1") (pin "3") (pinfunction "+IN_3") (pintype "input"))
      (node (ref "IC1") (pin "5") (pinfunction "+IN_5") (pintype "input"))
      (node (ref "IC2") (pin "3") (pinfunction "+IN_3") (pintype "input"))
      (node (ref "IC2") (pin "5") (pinfunction "+IN_5") (pintype "input"))
      (node (ref "IC4") (pin "3") (pinfunction "+IN_3") (pintype "input"))
      (node (ref "IC4") (pin "5") (pinfunction "+IN_5") (pintype "input"))
      (node (ref "R5") (pin "2") (pinfunction "2_2") (pintype "passive"))
      (node (ref "R6") (pin "1") (pinfunction "1_1") (pintype "passive"))
    )
    (net (code "75") (name "unconnected-(IC3-CBUS0-Pad23)") (class "Default")
      (node (ref "IC3") (pin "23") (pinfunction "CBUS0_23") (pintype "bidirectional"))
    )
    (net (code "76") (name "unconnected-(IC3-CBUS3-Pad14)") (class "Default")
      (node (ref "IC3") (pin "14") (pinfunction "CBUS3_14") (pintype "bidirectional"))
    )
    (net (code "77") (name "unconnected-(IC3-CBUS4-Pad12)") (class "Default")
      (node (ref "IC3") (pin "12") (pinfunction "CBUS4_12") (pintype "bidirectional"))
    )
    (net (code "78") (name "unconnected-(IC3-OSCO-Pad28)") (class "Default")
      (node (ref "IC3") (pin "28") (pinfunction "OSCO_28") (pintype "output"))
    )
    (net (code "79") (name "unconnected-(U1-GND-Pad22)") (class "Default")
      (node (ref "U1") (pin "22") (pinfunction "GND_22") (pintype "passive"))
    )
    (net (code "80") (name "unconnected-(U1-PB0-Pad14)") (class "Default")
      (node (ref "U1") (pin "14") (pinfunction "PB0_14") (pintype "bidirectional"))
    )
    (net (code "81") (name "unconnected-(U1-PB3-Pad17)") (class "Default")
      (node (ref "U1") (pin "17") (pinfunction "PB3_17") (pintype "bidirectional"))
    )
    (net (code "82") (name "unconnected-(U1-PB4-Pad18)") (class "Default")
      (node (ref "U1") (pin "18") (pinfunction "PB4_18") (pintype "bidirectional"))
    )
    (net (code "83") (name "unconnected-(U1-PB5-Pad19)") (class "Default")
      (node (ref "U1") (pin "19") (pinfunction "PB5_19") (pintype "bidirectional"))
    )
    (net (code "84") (name "unconnected-(U1-PC4-Pad27)") (class "Default")
      (node (ref "U1") (pin "27") (pinfunction "PC4_27") (pintype "bidirectional"))
    )
    (net (code "85") (name "unconnected-(U1-PC5-Pad28)") (class "Default")
      (node (ref "U1") (pin "28") (pinfunction "PC5_28") (pintype "bidirectional"))
    )
    (net (code "86") (name "unconnected-(U1-PD4-Pad6)") (class "Default")
      (node (ref "U1") (pin "6") (pinfunction "PD4_6") (pintype "bidirectional"))
    )
    (net (code "87") (name "unconnected-(U1-PD7-Pad13)") (class "Default")
      (node (ref "U1") (pin "13") (pinfunction "PD7_13") (pintype "bidirectional"))
    )
  )
)
